# Sheet1.net
KiCad netlist of a schematic drawn in Altium Designer
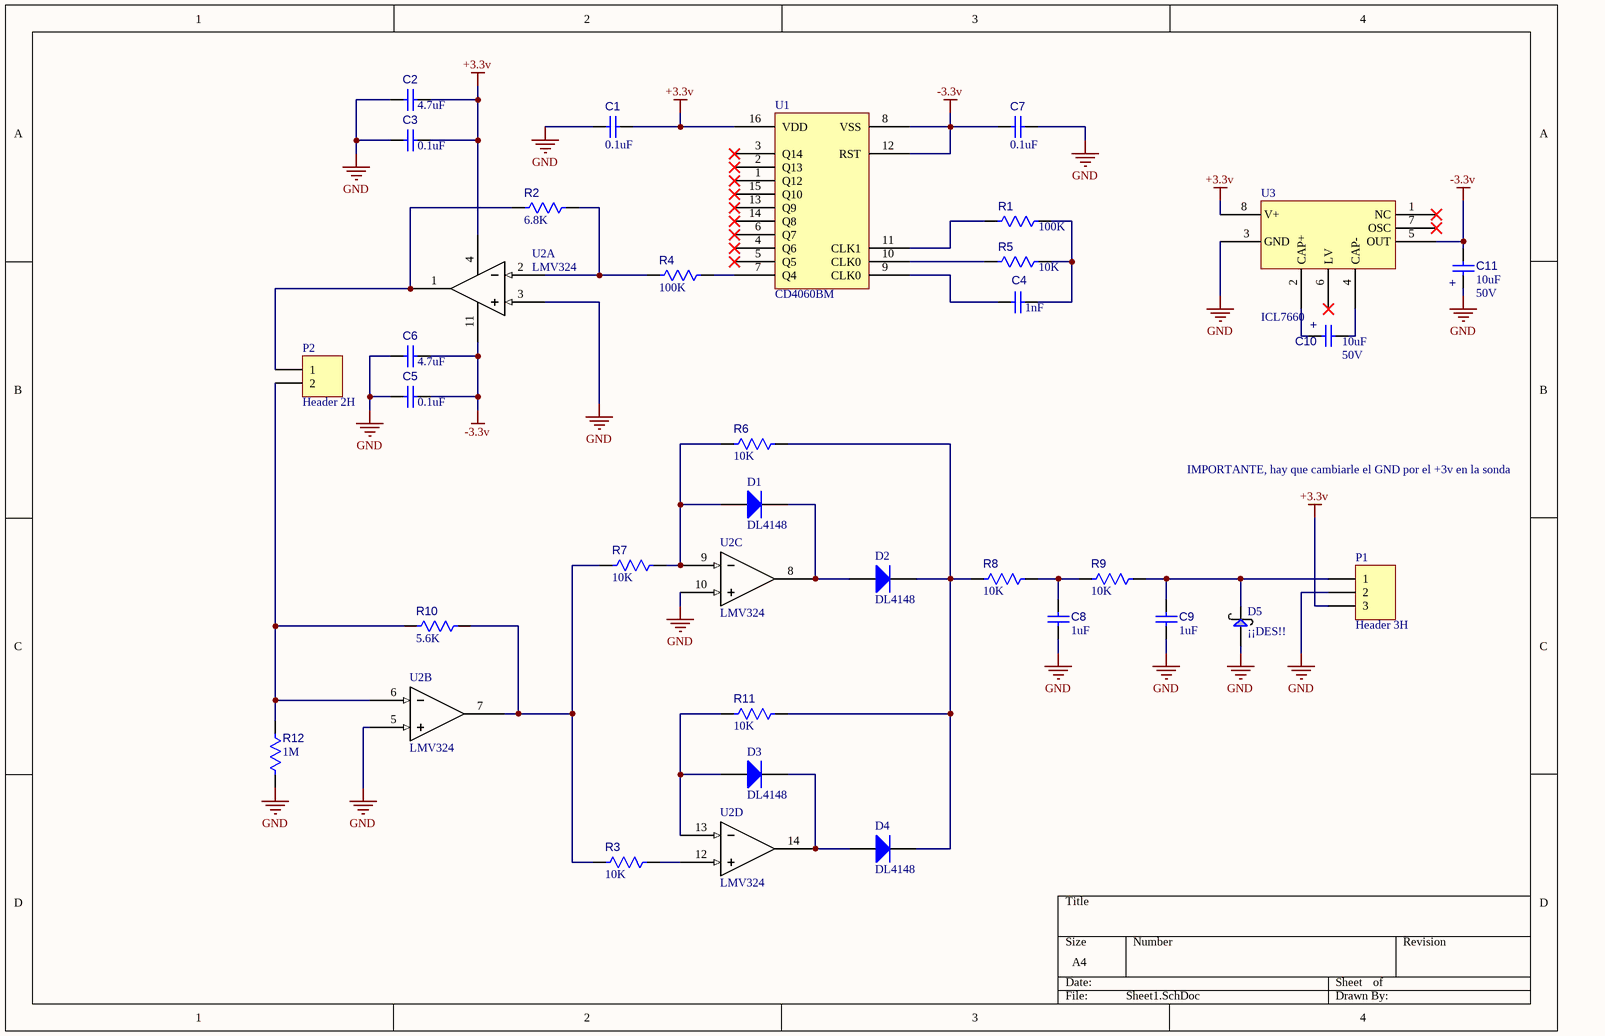
[diagram p0: Sheet1.SchDoc]

(export (version "E")
  (design (tool "Eeschema 10.0.6"))
  (components
    (comp (ref "C1")
      (value "0.1uF")
      (footprint "0603")
      (description "Cap")
      (fields (field (name "TOLERANCE") "±10%"))
      (libsource (lib "mylib") (part "Cap"))
    )
    (comp (ref "C2")
      (value "4.7uF")
      (footprint "0603")
      (description "Cap")
      (fields (field (name "TOLERANCE") "±10%"))
      (libsource (lib "mylib") (part "Cap"))
    )
    (comp (ref "C3")
      (value "0.1uF")
      (footprint "0603")
      (description "Cap")
      (fields (field (name "TOLERANCE") "±10%"))
      (libsource (lib "mylib") (part "Cap"))
    )
    (comp (ref "C4")
      (value "1nF")
      (footprint "0805")
      (description "Cap")
      (fields (field (name "TOLERANCE") "±10%"))
      (libsource (lib "mylib") (part "Cap"))
    )
    (comp (ref "C5")
      (value "0.1uF")
      (footprint "0603")
      (description "Cap")
      (fields (field (name "TOLERANCE") "±10%"))
      (libsource (lib "mylib") (part "Cap"))
    )
    (comp (ref "C6")
      (value "4.7uF")
      (footprint "0603")
      (description "Cap")
      (fields (field (name "TOLERANCE") "±10%"))
      (libsource (lib "mylib") (part "Cap"))
    )
    (comp (ref "C7")
      (value "0.1uF")
      (footprint "0603")
      (description "Cap")
      (fields (field (name "TOLERANCE") "±10%"))
      (libsource (lib "mylib") (part "Cap"))
    )
    (comp (ref "C8")
      (value "1uF")
      (footprint "0603")
      (description "Cap")
      (fields (field (name "TOLERANCE") "±10%"))
      (libsource (lib "mylib") (part "Cap"))
    )
    (comp (ref "C9")
      (value "1uF")
      (footprint "0603")
      (description "Cap")
      (fields (field (name "TOLERANCE") "±10%"))
      (libsource (lib "mylib") (part "Cap"))
    )
    (comp (ref "C10")
      (value "10uF")
      (footprint "CAPC3216x130N")
      (description "Cap")
      (fields
        (field (name "TOLERANCE") "±10%")
        (field (name "MANUFACTURER") "Panasonic")
        (field (name "VOLTAGE-RATED") "50V")
      )
      (libsource (lib "mylib") (part "Cap Pol"))
    )
    (comp (ref "C11")
      (value "10uF")
      (footprint "CAPC3216x130N")
      (description "Cap")
      (fields
        (field (name "TOLERANCE") "±10%")
        (field (name "MANUFACTURER") "Panasonic")
        (field (name "VOLTAGE-RATED") "50V")
      )
      (libsource (lib "mylib") (part "Cap Pol"))
    )
    (comp (ref "D1")
      (value "DL4148")
      (footprint "SOD80C")
      (description "Smal signal diode")
      (libsource (lib "mylib") (part "DL4148"))
    )
    (comp (ref "D2")
      (value "DL4148")
      (footprint "SOD80C")
      (description "Smal signal diode")
      (libsource (lib "mylib") (part "DL4148"))
    )
    (comp (ref "D3")
      (value "DL4148")
      (footprint "SOD80C")
      (description "Smal signal diode")
      (libsource (lib "mylib") (part "DL4148"))
    )
    (comp (ref "D4")
      (value "DL4148")
      (footprint "SOD80C")
      (description "Smal signal diode")
      (libsource (lib "mylib") (part "DL4148"))
    )
    (comp (ref "D5")
      (value "　DES!!")
      (footprint "DO214AC (SMA)")
      (description "SURFACE MOUNT SCHOTTKY BARRIER RECTIFIER 1N5829. Pueden ir varios de los de sech")
      (libsource (lib "mylib") (part "B340A"))
    )
    (comp (ref "P1")
      (value "Header 3H")
      (footprint "HDR1X3H")
      (description "Header, 3-Pin, Right Angle")
      (fields (field (name "PUBLISHER") "Altium Limited"))
      (libsource (lib "Miscellaneous Connectors") (part "Header 3H"))
    )
    (comp (ref "P2")
      (value "Header 2H")
      (footprint "HDR1X2H")
      (description "Header, 2-Pin, Right Angle")
      (fields (field (name "PUBLISHER") "Altium Limited"))
      (libsource (lib "Miscellaneous Connectors") (part "Header 2H"))
    )
    (comp (ref "R1")
      (value "100K")
      (footprint "0603")
      (description "Resistor")
      (fields (field (name "TOLERANCE") "1%"))
      (libsource (lib "mylib") (part "Res"))
    )
    (comp (ref "R2")
      (value "6.8K")
      (footprint "0805")
      (description "Resistor")
      (fields (field (name "TOLERANCE") "1%"))
      (libsource (lib "mylib") (part "Res"))
    )
    (comp (ref "R3")
      (value "10K")
      (footprint "0603")
      (description "Resistor")
      (fields (field (name "TOLERANCE") "1%"))
      (libsource (lib "mylib") (part "Res"))
    )
    (comp (ref "R4")
      (value "100K")
      (footprint "0603")
      (description "Resistor")
      (fields (field (name "TOLERANCE") "1%"))
      (libsource (lib "mylib") (part "Res"))
    )
    (comp (ref "R5")
      (value "10K")
      (footprint "0603")
      (description "Resistor")
      (fields (field (name "TOLERANCE") "1%"))
      (libsource (lib "mylib") (part "Res"))
    )
    (comp (ref "R6")
      (value "10K")
      (footprint "0603")
      (description "Resistor")
      (fields (field (name "TOLERANCE") "1%"))
      (libsource (lib "mylib") (part "Res"))
    )
    (comp (ref "R7")
      (value "10K")
      (footprint "0603")
      (description "Resistor")
      (fields (field (name "TOLERANCE") "1%"))
      (libsource (lib "mylib") (part "Res"))
    )
    (comp (ref "R8")
      (value "10K")
      (footprint "0603")
      (description "Resistor")
      (fields (field (name "TOLERANCE") "1%"))
      (libsource (lib "mylib") (part "Res"))
    )
    (comp (ref "R9")
      (value "10K")
      (footprint "0603")
      (description "Resistor")
      (fields (field (name "TOLERANCE") "1%"))
      (libsource (lib "mylib") (part "Res"))
    )
    (comp (ref "R10")
      (value "5.6K")
      (footprint "0805")
      (description "Resistor")
      (fields (field (name "TOLERANCE") "1%"))
      (libsource (lib "mylib") (part "Res"))
    )
    (comp (ref "R11")
      (value "10K")
      (footprint "0603")
      (description "Resistor")
      (fields (field (name "TOLERANCE") "1%"))
      (libsource (lib "mylib") (part "Res"))
    )
    (comp (ref "R12")
      (value "1M")
      (footprint "0603")
      (description "Resistor")
      (fields (field (name "TOLERANCE") "1%"))
      (libsource (lib "mylib") (part "Res"))
    )
    (comp (ref "U1")
      (value "CD4060BM")
      (footprint "SO-16_N")
      (description "IC Counter Binary Counter Element Bit Negative Edge 16-SOIC")
      (libsource (lib "mylib") (part "CD4060"))
    )
    (comp (ref "U2")
      (value "LMV324")
      (footprint "SO-14_N")
      (description "General Purpose Amplifier Circuit Rail-to-Rail 14-SOIC")
      (libsource (lib "mylib") (part "LMV324"))
    )
    (comp (ref "U3")
      (value "ICL7660")
      (footprint "SO8_N")
      (description "CMOS Voltage Converters, from positive to negative for an input range of +1.5V to +10.0V")
      (libsource (lib "mylib") (part "ICL7660"))
    )
  )
  (nets
    (net (code "1") (name "+3.3v") (class "Default")
      (node (ref "C1") (pin "2") (pinfunction "2_2") (pintype "passive"))
      (node (ref "C2") (pin "2") (pinfunction "2_2") (pintype "passive"))
      (node (ref "C3") (pin "2") (pinfunction "2_2") (pintype "passive"))
      (node (ref "P1") (pin "3") (pinfunction "3_3") (pintype "passive"))
      (node (ref "U1") (pin "16") (pinfunction "VDD_16") (pintype "passive"))
      (node (ref "U2") (pin "4") (pinfunction "4_4") (pintype "passive"))
      (node (ref "U3") (pin "8") (pinfunction "V+_8") (pintype "passive"))
    )
    (net (code "2") (name "-3.3v") (class "Default")
      (node (ref "C11") (pin "2") (pinfunction "2_2") (pintype "passive"))
      (node (ref "C5") (pin "2") (pinfunction "2_2") (pintype "passive"))
      (node (ref "C6") (pin "1") (pinfunction "1_1") (pintype "passive"))
      (node (ref "C7") (pin "1") (pinfunction "1_1") (pintype "passive"))
      (node (ref "U1") (pin "12") (pinfunction "RST_12") (pintype "passive"))
      (node (ref "U1") (pin "8") (pinfunction "VSS_8") (pintype "passive"))
      (node (ref "U2") (pin "11") (pinfunction "11_11") (pintype "passive"))
      (node (ref "U3") (pin "5") (pinfunction "OUT_5") (pintype "passive"))
    )
    (net (code "3") (name "GND") (class "Default")
      (node (ref "C1") (pin "1") (pinfunction "1_1") (pintype "passive"))
      (node (ref "C11") (pin "1") (pinfunction "1_1") (pintype "passive"))
      (node (ref "C2") (pin "1") (pinfunction "1_1") (pintype "passive"))
      (node (ref "C3") (pin "1") (pinfunction "1_1") (pintype "passive"))
      (node (ref "C5") (pin "1") (pinfunction "1_1") (pintype "passive"))
      (node (ref "C6") (pin "2") (pinfunction "2_2") (pintype "passive"))
      (node (ref "C7") (pin "2") (pinfunction "2_2") (pintype "passive"))
      (node (ref "C8") (pin "2") (pinfunction "2_2") (pintype "passive"))
      (node (ref "C9") (pin "2") (pinfunction "2_2") (pintype "passive"))
      (node (ref "D5") (pin "1") (pinfunction "1_1") (pintype "passive"))
      (node (ref "P1") (pin "2") (pinfunction "2_2") (pintype "passive"))
      (node (ref "R12") (pin "2") (pinfunction "2_2") (pintype "passive"))
      (node (ref "U2") (pin "10") (pinfunction "10_10") (pintype "input"))
      (node (ref "U2") (pin "3") (pinfunction "3_3") (pintype "input"))
      (node (ref "U2") (pin "5") (pinfunction "5_5") (pintype "input"))
      (node (ref "U3") (pin "3") (pinfunction "GND_3") (pintype "passive"))
    )
    (net (code "4") (name "Net-(C4-Pad1)") (class "Default")
      (node (ref "C4") (pin "1") (pinfunction "1_1") (pintype "passive"))
      (node (ref "R1") (pin "1") (pinfunction "1_1") (pintype "passive"))
      (node (ref "R5") (pin "1") (pinfunction "1_1") (pintype "passive"))
    )
    (net (code "5") (name "Net-(C4-Pad2)") (class "Default")
      (node (ref "C4") (pin "2") (pinfunction "2_2") (pintype "passive"))
      (node (ref "U1") (pin "9") (pinfunction "CLK0_9") (pintype "passive"))
    )
    (net (code "6") (name "Net-(C8-Pad1)") (class "Default")
      (node (ref "C8") (pin "1") (pinfunction "1_1") (pintype "passive"))
      (node (ref "R8") (pin "2") (pinfunction "2_2") (pintype "passive"))
      (node (ref "R9") (pin "1") (pinfunction "1_1") (pintype "passive"))
    )
    (net (code "7") (name "Net-(C9-Pad1)") (class "Default")
      (node (ref "C9") (pin "1") (pinfunction "1_1") (pintype "passive"))
      (node (ref "D5") (pin "2") (pinfunction "2_2") (pintype "passive"))
      (node (ref "P1") (pin "1") (pinfunction "1_1") (pintype "passive"))
      (node (ref "R9") (pin "2") (pinfunction "2_2") (pintype "passive"))
    )
    (net (code "8") (name "Net-(D1-A)") (class "Default")
      (node (ref "D1") (pin "1") (pinfunction "A_1") (pintype "passive"))
      (node (ref "R6") (pin "1") (pinfunction "1_1") (pintype "passive"))
      (node (ref "R7") (pin "2") (pinfunction "2_2") (pintype "passive"))
      (node (ref "U2") (pin "9") (pinfunction "9_9") (pintype "input"))
    )
    (net (code "9") (name "Net-(D1-K)") (class "Default")
      (node (ref "D1") (pin "2") (pinfunction "K_2") (pintype "passive"))
      (node (ref "D2") (pin "1") (pinfunction "A_1") (pintype "passive"))
      (node (ref "U2") (pin "8") (pinfunction "8_8") (pintype "passive"))
    )
    (net (code "10") (name "Net-(D2-K)") (class "Default")
      (node (ref "D2") (pin "2") (pinfunction "K_2") (pintype "passive"))
      (node (ref "D4") (pin "2") (pinfunction "K_2") (pintype "passive"))
      (node (ref "R11") (pin "2") (pinfunction "2_2") (pintype "passive"))
      (node (ref "R6") (pin "2") (pinfunction "2_2") (pintype "passive"))
      (node (ref "R8") (pin "1") (pinfunction "1_1") (pintype "passive"))
    )
    (net (code "11") (name "Net-(D3-A)") (class "Default")
      (node (ref "D3") (pin "1") (pinfunction "A_1") (pintype "passive"))
      (node (ref "R11") (pin "1") (pinfunction "1_1") (pintype "passive"))
      (node (ref "U2") (pin "13") (pinfunction "13_13") (pintype "input"))
    )
    (net (code "12") (name "Net-(D3-K)") (class "Default")
      (node (ref "D3") (pin "2") (pinfunction "K_2") (pintype "passive"))
      (node (ref "D4") (pin "1") (pinfunction "A_1") (pintype "passive"))
      (node (ref "U2") (pin "14") (pinfunction "14_14") (pintype "passive"))
    )
    (net (code "13") (name "Net-(P2-Pad1)") (class "Default")
      (node (ref "P2") (pin "1") (pinfunction "1_1") (pintype "passive"))
      (node (ref "R2") (pin "1") (pinfunction "1_1") (pintype "passive"))
      (node (ref "U2") (pin "1") (pinfunction "1_1") (pintype "passive"))
    )
    (net (code "14") (name "Net-(P2-Pad2)") (class "Default")
      (node (ref "P2") (pin "2") (pinfunction "2_2") (pintype "passive"))
      (node (ref "R10") (pin "1") (pinfunction "1_1") (pintype "passive"))
      (node (ref "R12") (pin "1") (pinfunction "1_1") (pintype "passive"))
      (node (ref "U2") (pin "6") (pinfunction "6_6") (pintype "input"))
    )
    (net (code "15") (name "Net-(R2-Pad2)") (class "Default")
      (node (ref "R2") (pin "2") (pinfunction "2_2") (pintype "passive"))
      (node (ref "R4") (pin "1") (pinfunction "1_1") (pintype "passive"))
      (node (ref "U2") (pin "2") (pinfunction "2_2") (pintype "input"))
    )
    (net (code "16") (name "Net-(R3-Pad2)") (class "Default")
      (node (ref "R3") (pin "2") (pinfunction "2_2") (pintype "passive"))
      (node (ref "U2") (pin "12") (pinfunction "12_12") (pintype "input"))
    )
    (net (code "17") (name "Net-(R5-Pad2)") (class "Default")
      (node (ref "R5") (pin "2") (pinfunction "2_2") (pintype "passive"))
      (node (ref "U1") (pin "10") (pinfunction "CLK0_10") (pintype "passive"))
    )
    (net (code "18") (name "Net-(R10-Pad2)") (class "Default")
      (node (ref "R10") (pin "2") (pinfunction "2_2") (pintype "passive"))
      (node (ref "R3") (pin "1") (pinfunction "1_1") (pintype "passive"))
      (node (ref "R7") (pin "1") (pinfunction "1_1") (pintype "passive"))
      (node (ref "U2") (pin "7") (pinfunction "7_7") (pintype "passive"))
    )
    (net (code "19") (name "Net-(U1-CLK1)") (class "Default")
      (node (ref "R1") (pin "2") (pinfunction "2_2") (pintype "passive"))
      (node (ref "U1") (pin "11") (pinfunction "CLK1_11") (pintype "passive"))
    )
    (net (code "20") (name "Net-(U1-Q4)") (class "Default")
      (node (ref "R4") (pin "2") (pinfunction "2_2") (pintype "passive"))
      (node (ref "U1") (pin "7") (pinfunction "Q4_7") (pintype "passive"))
    )
    (net (code "21") (name "Net-(U3-CAP+)") (class "Default")
      (node (ref "C10") (pin "1") (pinfunction "1_1") (pintype "passive"))
      (node (ref "U3") (pin "2") (pinfunction "CAP+_2") (pintype "passive"))
    )
    (net (code "22") (name "Net-(U3-CAP-)") (class "Default")
      (node (ref "C10") (pin "2") (pinfunction "2_2") (pintype "passive"))
      (node (ref "U3") (pin "4") (pinfunction "CAP-_4") (pintype "passive"))
    )
    (net (code "23") (name "unconnected-(U1-Q5-Pad5)") (class "Default")
      (node (ref "U1") (pin "5") (pinfunction "Q5_5") (pintype "passive+no_connect"))
    )
    (net (code "24") (name "unconnected-(U1-Q6-Pad4)") (class "Default")
      (node (ref "U1") (pin "4") (pinfunction "Q6_4") (pintype "passive+no_connect"))
    )
    (net (code "25") (name "unconnected-(U1-Q7-Pad6)") (class "Default")
      (node (ref "U1") (pin "6") (pinfunction "Q7_6") (pintype "passive+no_connect"))
    )
    (net (code "26") (name "unconnected-(U1-Q8-Pad14)") (class "Default")
      (node (ref "U1") (pin "14") (pinfunction "Q8_14") (pintype "passive+no_connect"))
    )
    (net (code "27") (name "unconnected-(U1-Q9-Pad13)") (class "Default")
      (node (ref "U1") (pin "13") (pinfunction "Q9_13") (pintype "passive+no_connect"))
    )
    (net (code "28") (name "unconnected-(U1-Q10-Pad15)") (class "Default")
      (node (ref "U1") (pin "15") (pinfunction "Q10_15") (pintype "passive+no_connect"))
    )
    (net (code "29") (name "unconnected-(U1-Q12-Pad1)") (class "Default")
      (node (ref "U1") (pin "1") (pinfunction "Q12_1") (pintype "passive+no_connect"))
    )
    (net (code "30") (name "unconnected-(U1-Q13-Pad2)") (class "Default")
      (node (ref "U1") (pin "2") (pinfunction "Q13_2") (pintype "passive+no_connect"))
    )
    (net (code "31") (name "unconnected-(U1-Q14-Pad3)") (class "Default")
      (node (ref "U1") (pin "3") (pinfunction "Q14_3") (pintype "passive+no_connect"))
    )
    (net (code "32") (name "unconnected-(U3-LV-Pad6)") (class "Default")
      (node (ref "U3") (pin "6") (pinfunction "LV_6") (pintype "passive+no_connect"))
    )
    (net (code "33") (name "unconnected-(U3-NC-Pad1)") (class "Default")
      (node (ref "U3") (pin "1") (pinfunction "NC_1") (pintype "passive+no_connect"))
    )
    (net (code "34") (name "unconnected-(U3-OSC-Pad7)") (class "Default")
      (node (ref "U3") (pin "7") (pinfunction "OSC_7") (pintype "passive+no_connect"))
    )
  )
)
